# 7segement4digits1badidea-huge-digits-mk-.net
KiCad netlist of a schematic drawn in EAGLE
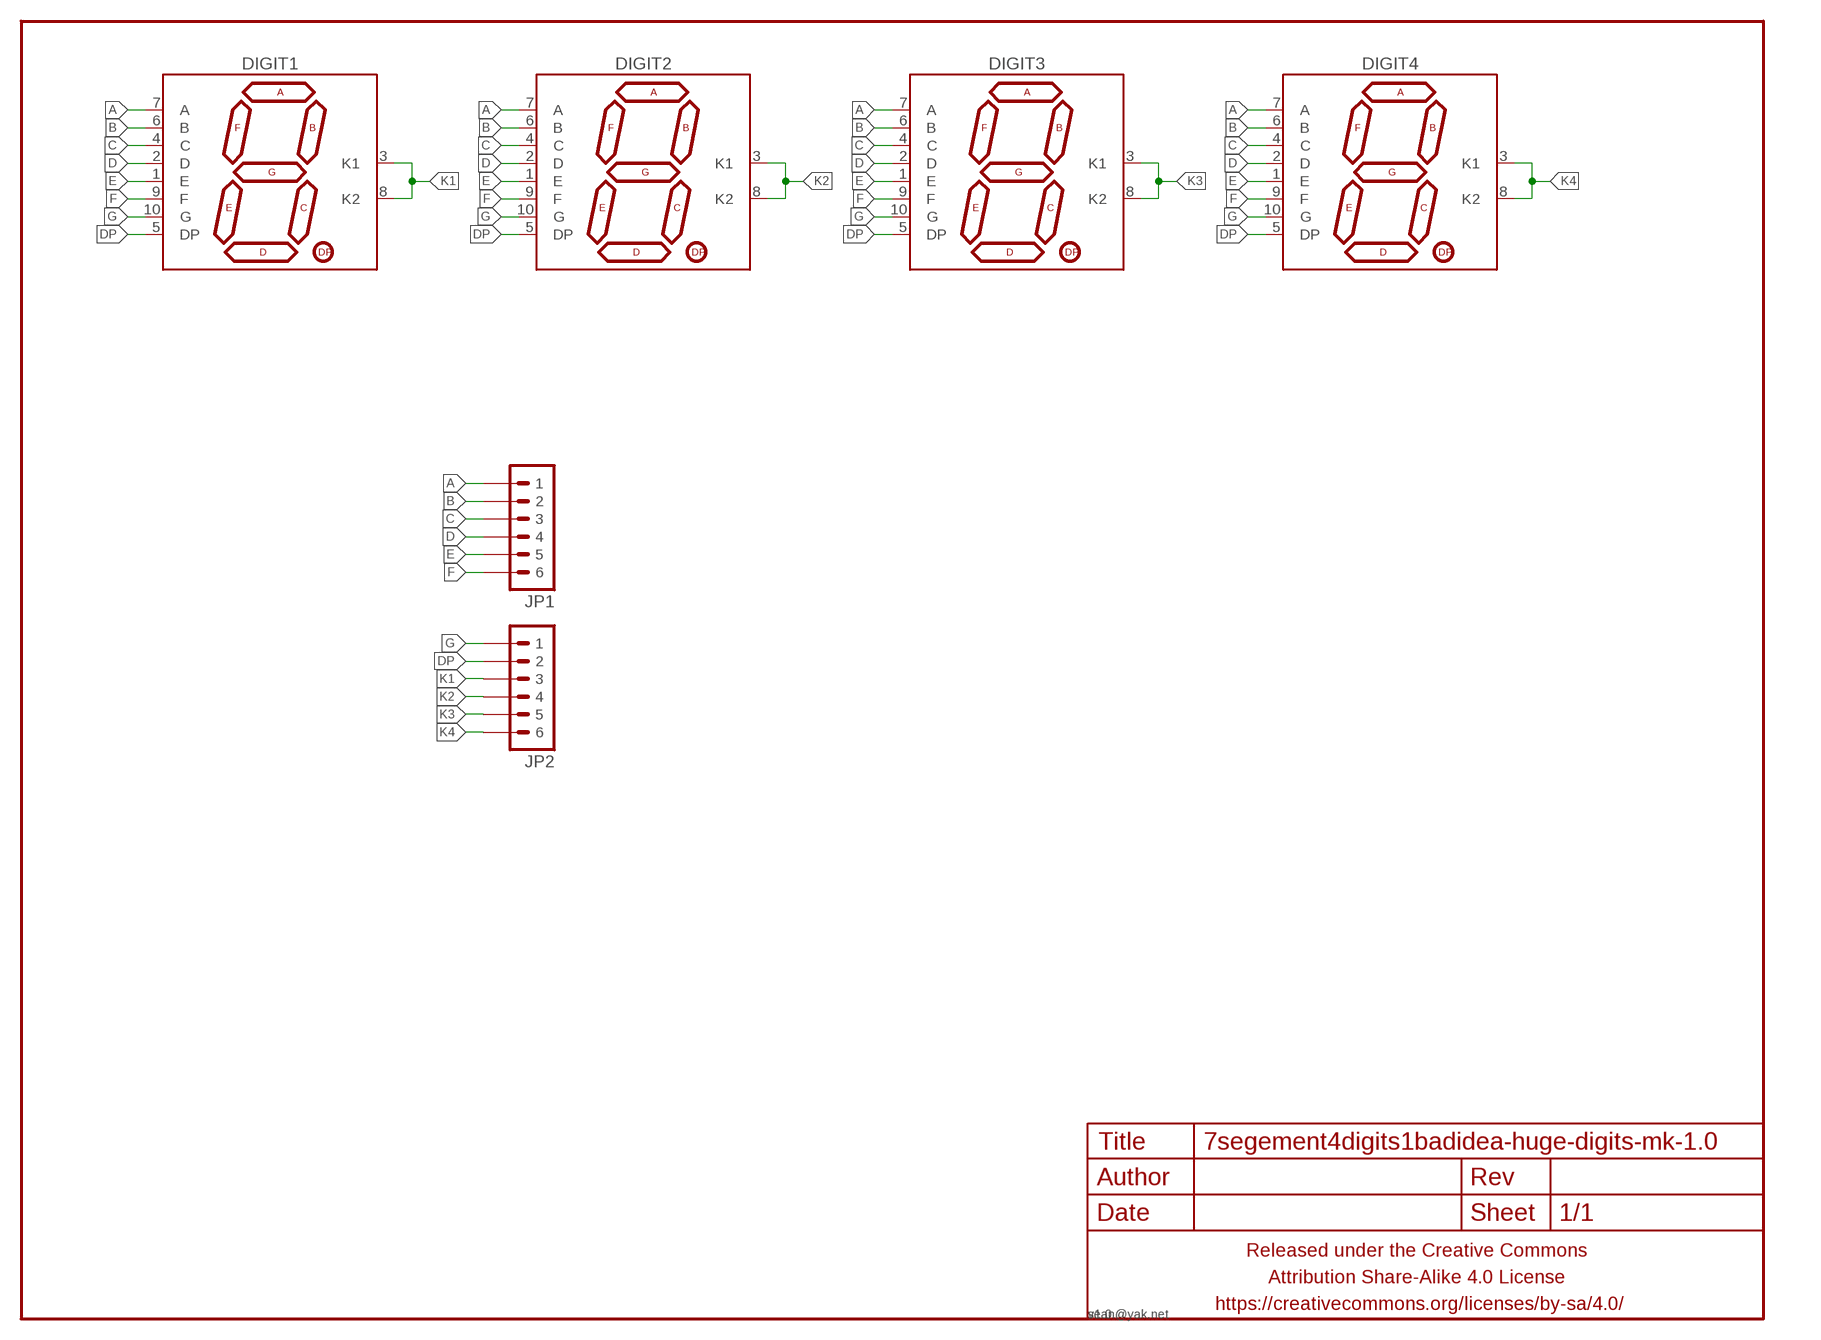
[diagram p0: schematic, sheet 1]

(export (version "E")
  (design (tool "Eeschema 10.0.6"))
  (components
    (comp (ref "DIGIT1")
      (value "7SEG_1DIGPTH-25.4MM")
      (footprint "eagle-import:7SEG_1DIG_25.4MM")
      (libsource (lib "eagle-import") (part "7SEG_1DIGPTH-25.4MM"))
    )
    (comp (ref "DIGIT2")
      (value "7SEG_1DIGPTH-25.4MM")
      (footprint "eagle-import:7SEG_1DIG_25.4MM")
      (libsource (lib "eagle-import") (part "7SEG_1DIGPTH-25.4MM"))
    )
    (comp (ref "DIGIT3")
      (value "7SEG_1DIGPTH-25.4MM")
      (footprint "eagle-import:7SEG_1DIG_25.4MM")
      (libsource (lib "eagle-import") (part "7SEG_1DIGPTH-25.4MM"))
    )
    (comp (ref "DIGIT4")
      (value "7SEG_1DIGPTH-25.4MM")
      (footprint "eagle-import:7SEG_1DIG_25.4MM")
      (libsource (lib "eagle-import") (part "7SEG_1DIGPTH-25.4MM"))
    )
    (comp (ref "FRAME1")
      (value "FRAME-LETTERNO_PACKAGE")
      (footprint "eagle-import:DUMMY")
      (fields
        (field (name "DESIGNER") "sean@yak.net")
        (field (name "VERSION") "v1.0")
        (field (name "DESIGNER_1") "sean@yak.net")
        (field (name "VERSION_1") "v1.0")
      )
      (libsource (lib "eagle-import") (part "FRAME-LETTERNO_PACKAGE"))
    )
    (comp (ref "JP1")
      (value "M06PTH_CENTERED")
      (footprint "eagle-import:1X06_CENTERED")
      (libsource (lib "eagle-import") (part "M06PTH_CENTERED"))
    )
    (comp (ref "JP2")
      (value "M06PTH_CENTERED")
      (footprint "eagle-import:1X06_CENTERED")
      (libsource (lib "eagle-import") (part "M06PTH_CENTERED"))
    )
  )
  (nets
    (net (code "1") (name "A") (class "Default")
      (node (ref "DIGIT1") (pin "7") (pinfunction "A_7") (pintype "bidirectional"))
      (node (ref "DIGIT2") (pin "7") (pinfunction "A_7") (pintype "bidirectional"))
      (node (ref "DIGIT3") (pin "7") (pinfunction "A_7") (pintype "bidirectional"))
      (node (ref "DIGIT4") (pin "7") (pinfunction "A_7") (pintype "bidirectional"))
      (node (ref "JP1") (pin "1") (pinfunction "1_1") (pintype "passive"))
    )
    (net (code "2") (name "B") (class "Default")
      (node (ref "DIGIT1") (pin "6") (pinfunction "B_6") (pintype "bidirectional"))
      (node (ref "DIGIT2") (pin "6") (pinfunction "B_6") (pintype "bidirectional"))
      (node (ref "DIGIT3") (pin "6") (pinfunction "B_6") (pintype "bidirectional"))
      (node (ref "DIGIT4") (pin "6") (pinfunction "B_6") (pintype "bidirectional"))
      (node (ref "JP1") (pin "2") (pinfunction "2_2") (pintype "passive"))
    )
    (net (code "3") (name "C") (class "Default")
      (node (ref "DIGIT1") (pin "4") (pinfunction "C_4") (pintype "bidirectional"))
      (node (ref "DIGIT2") (pin "4") (pinfunction "C_4") (pintype "bidirectional"))
      (node (ref "DIGIT3") (pin "4") (pinfunction "C_4") (pintype "bidirectional"))
      (node (ref "DIGIT4") (pin "4") (pinfunction "C_4") (pintype "bidirectional"))
      (node (ref "JP1") (pin "3") (pinfunction "3_3") (pintype "passive"))
    )
    (net (code "4") (name "D") (class "Default")
      (node (ref "DIGIT1") (pin "2") (pinfunction "D_2") (pintype "bidirectional"))
      (node (ref "DIGIT2") (pin "2") (pinfunction "D_2") (pintype "bidirectional"))
      (node (ref "DIGIT3") (pin "2") (pinfunction "D_2") (pintype "bidirectional"))
      (node (ref "DIGIT4") (pin "2") (pinfunction "D_2") (pintype "bidirectional"))
      (node (ref "JP1") (pin "4") (pinfunction "4_4") (pintype "passive"))
    )
    (net (code "5") (name "DP") (class "Default")
      (node (ref "DIGIT1") (pin "5") (pinfunction "DP_5") (pintype "bidirectional"))
      (node (ref "DIGIT2") (pin "5") (pinfunction "DP_5") (pintype "bidirectional"))
      (node (ref "DIGIT3") (pin "5") (pinfunction "DP_5") (pintype "bidirectional"))
      (node (ref "DIGIT4") (pin "5") (pinfunction "DP_5") (pintype "bidirectional"))
      (node (ref "JP2") (pin "2") (pinfunction "2_2") (pintype "passive"))
    )
    (net (code "6") (name "E") (class "Default")
      (node (ref "DIGIT1") (pin "1") (pinfunction "E_1") (pintype "bidirectional"))
      (node (ref "DIGIT2") (pin "1") (pinfunction "E_1") (pintype "bidirectional"))
      (node (ref "DIGIT3") (pin "1") (pinfunction "E_1") (pintype "bidirectional"))
      (node (ref "DIGIT4") (pin "1") (pinfunction "E_1") (pintype "bidirectional"))
      (node (ref "JP1") (pin "5") (pinfunction "5_5") (pintype "passive"))
    )
    (net (code "7") (name "F") (class "Default")
      (node (ref "DIGIT1") (pin "9") (pinfunction "F_9") (pintype "bidirectional"))
      (node (ref "DIGIT2") (pin "9") (pinfunction "F_9") (pintype "bidirectional"))
      (node (ref "DIGIT3") (pin "9") (pinfunction "F_9") (pintype "bidirectional"))
      (node (ref "DIGIT4") (pin "9") (pinfunction "F_9") (pintype "bidirectional"))
      (node (ref "JP1") (pin "6") (pinfunction "6_6") (pintype "passive"))
    )
    (net (code "8") (name "G") (class "Default")
      (node (ref "DIGIT1") (pin "10") (pinfunction "G_10") (pintype "bidirectional"))
      (node (ref "DIGIT2") (pin "10") (pinfunction "G_10") (pintype "bidirectional"))
      (node (ref "DIGIT3") (pin "10") (pinfunction "G_10") (pintype "bidirectional"))
      (node (ref "DIGIT4") (pin "10") (pinfunction "G_10") (pintype "bidirectional"))
      (node (ref "JP2") (pin "1") (pinfunction "1_1") (pintype "passive"))
    )
    (net (code "9") (name "K1") (class "Default")
      (node (ref "DIGIT1") (pin "3") (pinfunction "K1_3") (pintype "bidirectional"))
      (node (ref "DIGIT1") (pin "8") (pinfunction "K2_8") (pintype "bidirectional"))
      (node (ref "JP2") (pin "3") (pinfunction "3_3") (pintype "passive"))
    )
    (net (code "10") (name "K2") (class "Default")
      (node (ref "DIGIT2") (pin "3") (pinfunction "K1_3") (pintype "bidirectional"))
      (node (ref "DIGIT2") (pin "8") (pinfunction "K2_8") (pintype "bidirectional"))
      (node (ref "JP2") (pin "4") (pinfunction "4_4") (pintype "passive"))
    )
    (net (code "11") (name "K3") (class "Default")
      (node (ref "DIGIT3") (pin "3") (pinfunction "K1_3") (pintype "bidirectional"))
      (node (ref "DIGIT3") (pin "8") (pinfunction "K2_8") (pintype "bidirectional"))
      (node (ref "JP2") (pin "5") (pinfunction "5_5") (pintype "passive"))
    )
    (net (code "12") (name "K4") (class "Default")
      (node (ref "DIGIT4") (pin "3") (pinfunction "K1_3") (pintype "bidirectional"))
      (node (ref "DIGIT4") (pin "8") (pinfunction "K2_8") (pintype "bidirectional"))
      (node (ref "JP2") (pin "6") (pinfunction "6_6") (pintype "passive"))
    )
  )
)
